# gripper-rev-2a.net
KiCad netlist of a schematic drawn in EAGLE
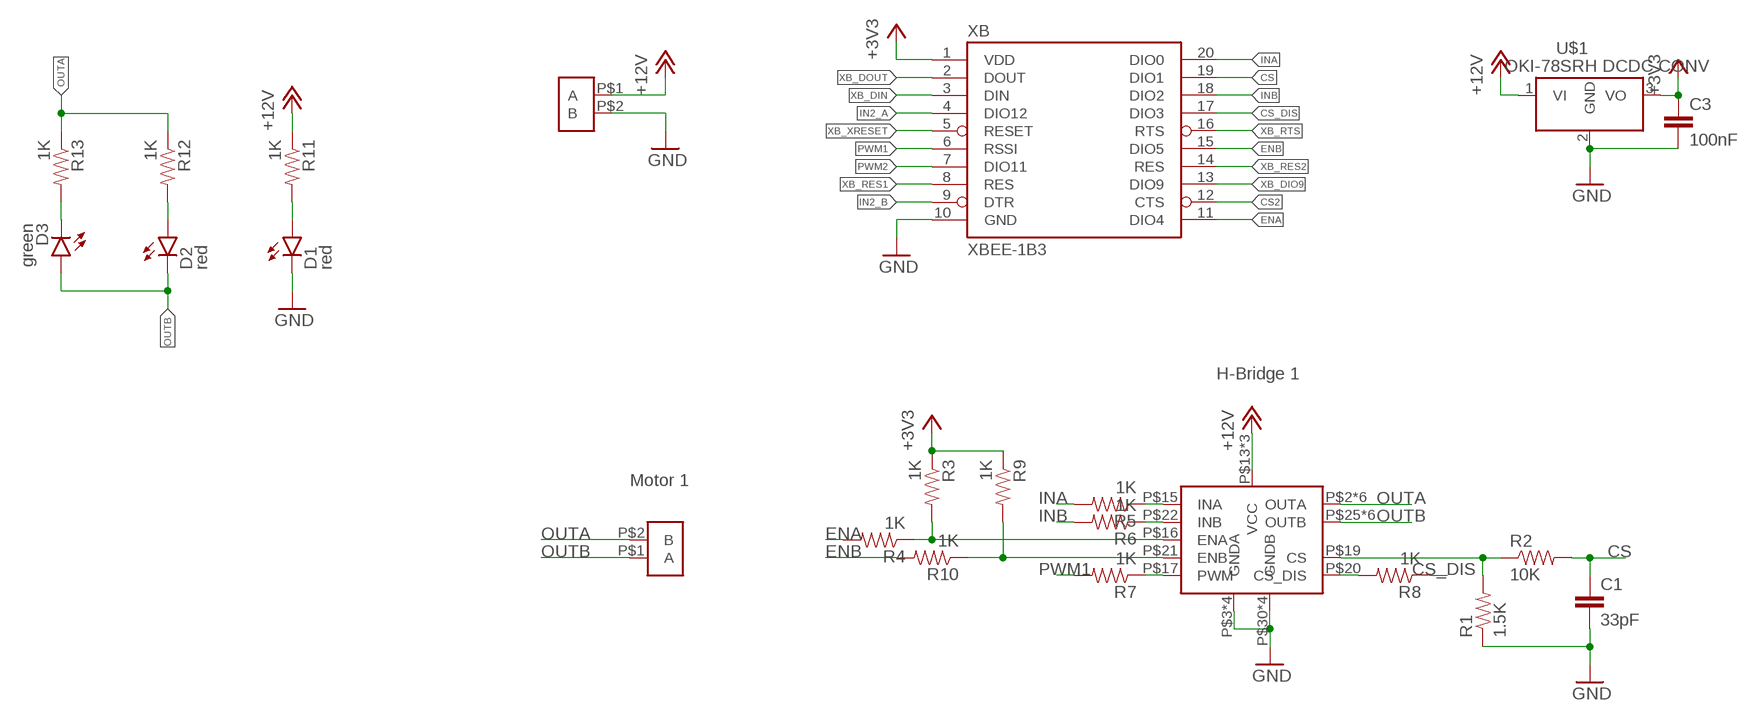
[diagram p0: schematic, sheet 1]

(export (version "E")
  (design (tool "Eeschema 10.0.6"))
  (components
    (comp (ref "C1")
      (value "33pF")
      (footprint "eagle-import:0603-CAP")
      (libsource (lib "eagle-import") (part "CAP0603-CAP"))
    )
    (comp (ref "C3")
      (value "100nF")
      (footprint "eagle-import:0603-CAP")
      (libsource (lib "eagle-import") (part "10NF/10000PF-50V-10%(0603)"))
    )
    (comp (ref "D1")
      (value "red")
      (footprint "eagle-import:LED-0603")
      (libsource (lib "eagle-import") (part "LED0603"))
    )
    (comp (ref "D2")
      (value "red")
      (footprint "eagle-import:LED-0603")
      (libsource (lib "eagle-import") (part "LED0603"))
    )
    (comp (ref "D3")
      (value "green")
      (footprint "eagle-import:LED-0603")
      (libsource (lib "eagle-import") (part "LED0603"))
    )
    (comp (ref "R1")
      (value "1.5K")
      (footprint "eagle-import:0603-RES")
      (libsource (lib "eagle-import") (part "RESISTOR0603"))
    )
    (comp (ref "R2")
      (value "10K")
      (footprint "eagle-import:0603-RES")
      (libsource (lib "eagle-import") (part "RESISTOR0603"))
    )
    (comp (ref "R3")
      (value "1K")
      (footprint "eagle-import:0603-RES")
      (libsource (lib "eagle-import") (part "RESISTOR0603"))
    )
    (comp (ref "R4")
      (value "1K")
      (footprint "eagle-import:0603-RES")
      (libsource (lib "eagle-import") (part "RESISTOR0603"))
    )
    (comp (ref "R5")
      (value "1K")
      (footprint "eagle-import:0603-RES")
      (libsource (lib "eagle-import") (part "RESISTOR0603"))
    )
    (comp (ref "R6")
      (value "1K")
      (footprint "eagle-import:0603-RES")
      (libsource (lib "eagle-import") (part "RESISTOR0603"))
    )
    (comp (ref "R7")
      (value "1K")
      (footprint "eagle-import:0603-RES")
      (libsource (lib "eagle-import") (part "RESISTOR0603"))
    )
    (comp (ref "R8")
      (value "1K")
      (footprint "eagle-import:0603-RES")
      (libsource (lib "eagle-import") (part "RESISTOR0603"))
    )
    (comp (ref "R9")
      (value "1K")
      (footprint "eagle-import:0603-RES")
      (libsource (lib "eagle-import") (part "RESISTOR0603"))
    )
    (comp (ref "R10")
      (value "1K")
      (footprint "eagle-import:0603-RES")
      (libsource (lib "eagle-import") (part "RESISTOR0603"))
    )
    (comp (ref "R11")
      (value "1K")
      (footprint "eagle-import:0603-RES")
      (libsource (lib "eagle-import") (part "RESISTOR0603"))
    )
    (comp (ref "R12")
      (value "1K")
      (footprint "eagle-import:0603-RES")
      (libsource (lib "eagle-import") (part "RESISTOR0603"))
    )
    (comp (ref "R13")
      (value "1K")
      (footprint "eagle-import:0603-RES")
      (libsource (lib "eagle-import") (part "RESISTOR0603"))
    )
    (comp (ref "U$1")
      (value "Q_OKI-78SR")
      (footprint "eagle-import:OKI-78SR_HORIZ")
      (libsource (lib "eagle-import") (part "Q_OKI-78SR"))
    )
    (comp (ref "U$4")
      (value "VNH5180A")
      (footprint "eagle-import:POWERSSO-36_TP")
      (libsource (lib "eagle-import") (part "VNH5180A"))
    )
    (comp (ref "U$6")
      (value "TE_2POS_SCREW_TERM")
      (footprint "eagle-import:TE_2POS-5MM_SCREW_TERM")
      (libsource (lib "eagle-import") (part "TE_2POS_SCREW_TERM"))
    )
    (comp (ref "U$8")
      (value "TE_2POS_SCREW_TERM")
      (footprint "eagle-import:TE_2POS-5MM_SCREW_TERM")
      (libsource (lib "eagle-import") (part "TE_2POS_SCREW_TERM"))
    )
    (comp (ref "XB")
      (value "XBEE-1B3")
      (footprint "eagle-import:XBEE-SMD")
      (libsource (lib "eagle-import") (part "XBEE-1B3"))
    )
  )
  (nets
    (net (code "1") (name "+3V3") (class "Default")
      (node (ref "C3") (pin "1") (pinfunction "1_1") (pintype "passive"))
      (node (ref "R3") (pin "1") (pinfunction "1_1") (pintype "passive"))
      (node (ref "R9") (pin "1") (pinfunction "1_1") (pintype "passive"))
      (node (ref "U$1") (pin "3") (pinfunction "VO_3") (pintype "bidirectional"))
      (node (ref "XB") (pin "1") (pinfunction "VDD_1") (pintype "power_in"))
    )
    (net (code "2") (name "+12V") (class "Default")
      (node (ref "R11") (pin "1") (pinfunction "1_1") (pintype "passive"))
      (node (ref "U$1") (pin "1") (pinfunction "VI_1") (pintype "bidirectional"))
      (node (ref "U$4") (pin "P$13") (pinfunction "VCC_P$13") (pintype "bidirectional"))
      (node (ref "U$4") (pin "P$24") (pinfunction "VCC_P$24") (pintype "bidirectional"))
      (node (ref "U$4") (pin "SLUG1") (pinfunction "VCC_SLUG1") (pintype "bidirectional"))
      (node (ref "U$6") (pin "P$1") (pinfunction "A_P$1") (pintype "bidirectional"))
    )
    (net (code "3") (name "CS") (class "Default")
      (node (ref "C1") (pin "1") (pinfunction "1_1") (pintype "passive"))
      (node (ref "R2") (pin "2") (pinfunction "2_2") (pintype "passive"))
      (node (ref "XB") (pin "19") (pinfunction "DIO1_19") (pintype "bidirectional"))
    )
    (net (code "4") (name "CS2") (class "Default")
      (node (ref "XB") (pin "12") (pinfunction "CTS_12") (pintype "output"))
    )
    (net (code "5") (name "CS_DIS") (class "Default")
      (node (ref "R8") (pin "1") (pinfunction "1_1") (pintype "passive"))
      (node (ref "XB") (pin "17") (pinfunction "DIO3_17") (pintype "bidirectional"))
    )
    (net (code "6") (name "ENA") (class "Default")
      (node (ref "R4") (pin "2") (pinfunction "2_2") (pintype "passive"))
      (node (ref "XB") (pin "11") (pinfunction "DIO4_11") (pintype "bidirectional"))
    )
    (net (code "7") (name "ENB") (class "Default")
      (node (ref "R10") (pin "2") (pinfunction "2_2") (pintype "passive"))
      (node (ref "XB") (pin "15") (pinfunction "DIO5_15") (pintype "bidirectional"))
    )
    (net (code "8") (name "GND") (class "Default")
      (node (ref "C1") (pin "2") (pinfunction "2_2") (pintype "passive"))
      (node (ref "C3") (pin "2") (pinfunction "2_2") (pintype "passive"))
      (node (ref "D1") (pin "C") (pinfunction "C_C") (pintype "passive"))
      (node (ref "R1") (pin "1") (pinfunction "1_1") (pintype "passive"))
      (node (ref "U$1") (pin "2") (pinfunction "GND_2") (pintype "bidirectional"))
      (node (ref "U$4") (pin "P$3") (pinfunction "GNDA_P$3") (pintype "bidirectional"))
      (node (ref "U$4") (pin "P$30") (pinfunction "GNDB_P$30") (pintype "bidirectional"))
      (node (ref "U$4") (pin "P$31") (pinfunction "GNDB_P$31") (pintype "bidirectional"))
      (node (ref "U$4") (pin "P$33") (pinfunction "GNDB_P$33") (pintype "bidirectional"))
      (node (ref "U$4") (pin "P$34") (pinfunction "GNDB_P$34") (pintype "bidirectional"))
      (node (ref "U$4") (pin "P$4") (pinfunction "GNDA_P$4") (pintype "bidirectional"))
      (node (ref "U$4") (pin "P$6") (pinfunction "GNDA_P$6") (pintype "bidirectional"))
      (node (ref "U$4") (pin "P$7") (pinfunction "GNDA_P$7") (pintype "bidirectional"))
      (node (ref "U$6") (pin "P$2") (pinfunction "B_P$2") (pintype "bidirectional"))
      (node (ref "XB") (pin "10") (pinfunction "GND_10") (pintype "power_in"))
    )
    (net (code "9") (name "IN2_A") (class "Default")
      (node (ref "XB") (pin "4") (pinfunction "DIO12_4") (pintype "bidirectional"))
    )
    (net (code "10") (name "IN2_B") (class "Default")
      (node (ref "XB") (pin "9") (pinfunction "DTR_9") (pintype "bidirectional"))
    )
    (net (code "11") (name "INA") (class "Default")
      (node (ref "R5") (pin "2") (pinfunction "2_2") (pintype "passive"))
      (node (ref "XB") (pin "20") (pinfunction "DIO0_20") (pintype "bidirectional"))
    )
    (net (code "12") (name "INB") (class "Default")
      (node (ref "R6") (pin "2") (pinfunction "2_2") (pintype "passive"))
      (node (ref "XB") (pin "18") (pinfunction "DIO2_18") (pintype "bidirectional"))
    )
    (net (code "13") (name "Net-(D1-PadA)") (class "Default")
      (node (ref "D1") (pin "A") (pinfunction "A_A") (pintype "passive"))
      (node (ref "R11") (pin "2") (pinfunction "2_2") (pintype "passive"))
    )
    (net (code "14") (name "Net-(D2-PadA)") (class "Default")
      (node (ref "D2") (pin "A") (pinfunction "A_A") (pintype "passive"))
      (node (ref "R12") (pin "2") (pinfunction "2_2") (pintype "passive"))
    )
    (net (code "15") (name "Net-(D3-PadC)") (class "Default")
      (node (ref "D3") (pin "C") (pinfunction "C_C") (pintype "passive"))
      (node (ref "R13") (pin "2") (pinfunction "2_2") (pintype "passive"))
    )
    (net (code "16") (name "Net-(U$4-CS)") (class "Default")
      (node (ref "R1") (pin "2") (pinfunction "2_2") (pintype "passive"))
      (node (ref "R2") (pin "1") (pinfunction "1_1") (pintype "passive"))
      (node (ref "U$4") (pin "P$19") (pinfunction "CS_P$19") (pintype "bidirectional"))
    )
    (net (code "17") (name "Net-(U$4-CS_DIS)") (class "Default")
      (node (ref "R8") (pin "2") (pinfunction "2_2") (pintype "passive"))
      (node (ref "U$4") (pin "P$20") (pinfunction "CS_DIS_P$20") (pintype "bidirectional"))
    )
    (net (code "18") (name "Net-(U$4-ENA)") (class "Default")
      (node (ref "R3") (pin "2") (pinfunction "2_2") (pintype "passive"))
      (node (ref "R4") (pin "1") (pinfunction "1_1") (pintype "passive"))
      (node (ref "U$4") (pin "P$16") (pinfunction "ENA_P$16") (pintype "bidirectional"))
    )
    (net (code "19") (name "Net-(U$4-ENB)") (class "Default")
      (node (ref "R10") (pin "1") (pinfunction "1_1") (pintype "passive"))
      (node (ref "R9") (pin "2") (pinfunction "2_2") (pintype "passive"))
      (node (ref "U$4") (pin "P$21") (pinfunction "ENB_P$21") (pintype "bidirectional"))
    )
    (net (code "20") (name "Net-(U$4-INA)") (class "Default")
      (node (ref "R5") (pin "1") (pinfunction "1_1") (pintype "passive"))
      (node (ref "U$4") (pin "P$15") (pinfunction "INA_P$15") (pintype "bidirectional"))
    )
    (net (code "21") (name "Net-(U$4-INB)") (class "Default")
      (node (ref "R6") (pin "1") (pinfunction "1_1") (pintype "passive"))
      (node (ref "U$4") (pin "P$22") (pinfunction "INB_P$22") (pintype "bidirectional"))
    )
    (net (code "22") (name "Net-(U$4-PWM)") (class "Default")
      (node (ref "R7") (pin "1") (pinfunction "1_1") (pintype "passive"))
      (node (ref "U$4") (pin "P$17") (pinfunction "PWM_P$17") (pintype "bidirectional"))
    )
    (net (code "23") (name "OUTA") (class "Default")
      (node (ref "R12") (pin "1") (pinfunction "1_1") (pintype "passive"))
      (node (ref "R13") (pin "1") (pinfunction "1_1") (pintype "passive"))
      (node (ref "U$4") (pin "P$10") (pinfunction "OUTA_P$10") (pintype "bidirectional"))
      (node (ref "U$4") (pin "P$11") (pinfunction "OUTA_P$11") (pintype "bidirectional"))
      (node (ref "U$4") (pin "P$12") (pinfunction "OUTA_P$12") (pintype "bidirectional"))
      (node (ref "U$4") (pin "P$2") (pinfunction "OUTA_P$2") (pintype "bidirectional"))
      (node (ref "U$4") (pin "P$8") (pinfunction "OUTA_P$8") (pintype "bidirectional"))
      (node (ref "U$4") (pin "SLUG2") (pinfunction "OUTA_SLUG2") (pintype "bidirectional"))
      (node (ref "U$8") (pin "P$2") (pinfunction "B_P$2") (pintype "bidirectional"))
    )
    (net (code "24") (name "OUTB") (class "Default")
      (node (ref "D2") (pin "C") (pinfunction "C_C") (pintype "passive"))
      (node (ref "D3") (pin "A") (pinfunction "A_A") (pintype "passive"))
      (node (ref "U$4") (pin "P$25") (pinfunction "OUTB_P$25") (pintype "bidirectional"))
      (node (ref "U$4") (pin "P$26") (pinfunction "OUTB_P$26") (pintype "bidirectional"))
      (node (ref "U$4") (pin "P$27") (pinfunction "OUTB_P$27") (pintype "bidirectional"))
      (node (ref "U$4") (pin "P$29") (pinfunction "OUTB_P$29") (pintype "bidirectional"))
      (node (ref "U$4") (pin "P$35") (pinfunction "OUTB_P$35") (pintype "bidirectional"))
      (node (ref "U$4") (pin "SLUG3") (pinfunction "OUTB_SLUG3") (pintype "bidirectional"))
      (node (ref "U$8") (pin "P$1") (pinfunction "A_P$1") (pintype "bidirectional"))
    )
    (net (code "25") (name "PWM1") (class "Default")
      (node (ref "R7") (pin "2") (pinfunction "2_2") (pintype "passive"))
      (node (ref "XB") (pin "6") (pinfunction "RSSI_6") (pintype "bidirectional"))
    )
    (net (code "26") (name "PWM2") (class "Default")
      (node (ref "XB") (pin "7") (pinfunction "DIO11_7") (pintype "bidirectional"))
    )
    (net (code "27") (name "XB_DIN") (class "Default")
      (node (ref "XB") (pin "3") (pinfunction "DIN_3") (pintype "input"))
    )
    (net (code "28") (name "XB_DIO9") (class "Default")
      (node (ref "XB") (pin "13") (pinfunction "DIO9_13") (pintype "bidirectional"))
    )
    (net (code "29") (name "XB_DOUT") (class "Default")
      (node (ref "XB") (pin "2") (pinfunction "DOUT_2") (pintype "output"))
    )
    (net (code "30") (name "XB_RES1") (class "Default")
      (node (ref "XB") (pin "8") (pinfunction "RES_8") (pintype "bidirectional"))
    )
    (net (code "31") (name "XB_RES2") (class "Default")
      (node (ref "XB") (pin "14") (pinfunction "RES_14") (pintype "bidirectional"))
    )
    (net (code "32") (name "XB_RTS") (class "Default")
      (node (ref "XB") (pin "16") (pinfunction "RTS_16") (pintype "input"))
    )
    (net (code "33") (name "XB_XRESET") (class "Default")
      (node (ref "XB") (pin "5") (pinfunction "RESET_5") (pintype "input"))
    )
  )
)
